# LED_Driver_-_2.net
KiCad netlist of a schematic drawn in Altium Designer
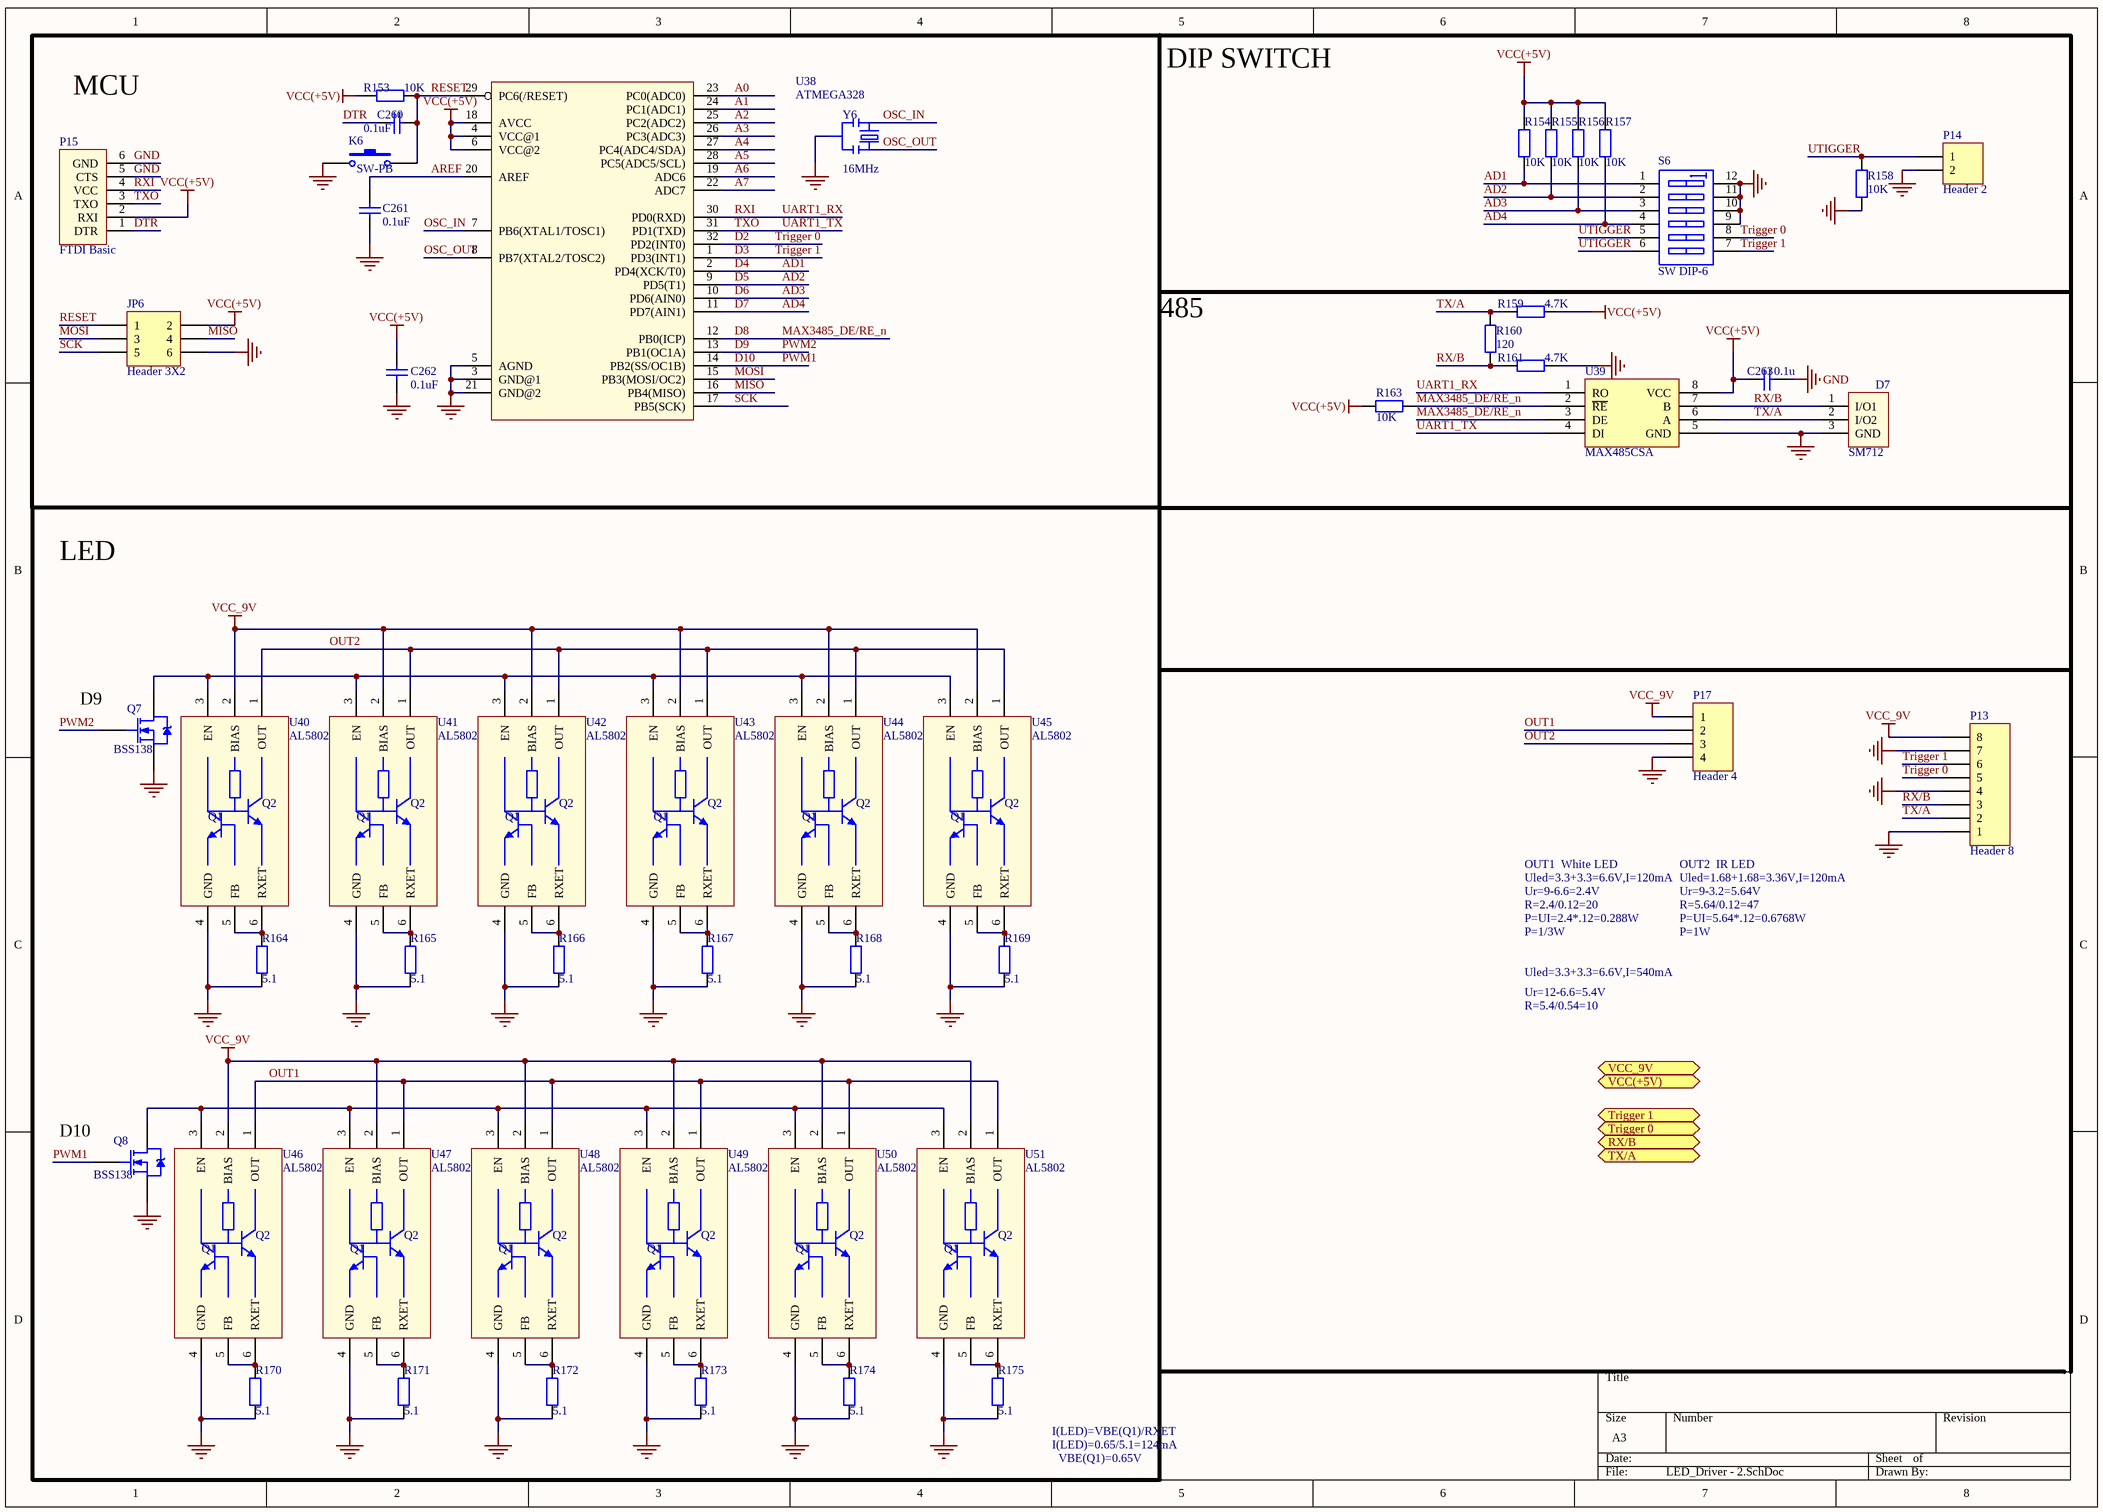
[diagram p0: LED_Driver - 2.SchDoc]

(export (version "E")
  (design (tool "Eeschema 10.0.6"))
  (components
    (comp (ref "C260")
      (value "0.1uF")
      (footprint "C0603")
      (description "Capacitor")
      (fields (field (name "IPARTNUMBER") "C100nF25V10%X7R") (field (name "VOLTAGE") "25V"))
      (libsource (lib "Schlib1") (part "CAP SMT C100nF25V10%X7R"))
    )
    (comp (ref "C261")
      (value "0.1uF")
      (footprint "C0603")
      (description "Capacitor")
      (fields (field (name "IPARTNUMBER") "C100nF25V10%X7R") (field (name "VOLTAGE") "25V"))
      (libsource (lib "Schlib1") (part "CAP SMT C100nF25V10%X7R"))
    )
    (comp (ref "C262")
      (value "0.1uF")
      (footprint "C0603")
      (description "Capacitor")
      (fields (field (name "IPARTNUMBER") "C100nF25V10%X7R") (field (name "VOLTAGE") "25V"))
      (libsource (lib "Schlib1") (part "CAP SMT C100nF25V10%X7R"))
    )
    (comp (ref "C263")
      (value "0.1u")
      (footprint "C0603")
      (description "Capacitor")
      (fields (field (name "PUBLISHER") "Altium Limited"))
      (libsource (lib "Miscellaneous Devices") (part "Cap"))
    )
    (comp (ref "D7")
      (value "SM712")
      (footprint "SOT23-3")
      (libsource (lib "STM32F4_CAM V2.0") (part "SM712"))
    )
    (comp (ref "JP6")
      (value "Header 3X2")
      (footprint "MHDR1X6")
      (description "Header, 3-Pin, Dual row")
      (fields (field (name "PUBLISHER") "Altium Limited"))
      (libsource (lib "Miscellaneous Connectors") (part "Header 3X2"))
    )
    (comp (ref "K6")
      (value "SW-PB")
      (footprint "157SW")
      (description "Switch")
      (fields (field (name "PUBLISHER") "Altium Limited"))
      (libsource (lib "Miscellaneous Devices") (part "SW-PB"))
    )
    (comp (ref "P13")
      (value "Header 8")
      (footprint "SH_1.25MM*8")
      (description "Header, 8-Pin")
      (fields (field (name "PUBLISHER") "Altium Limited"))
      (libsource (lib "Miscellaneous Connectors") (part "Header 8"))
    )
    (comp (ref "P14")
      (value "Header 2")
      (footprint "HDR1X2")
      (description "Header, 2-Pin")
      (fields (field (name "PUBLISHER") "Altium Limited"))
      (libsource (lib "Miscellaneous Connectors") (part "Header 2"))
    )
    (comp (ref "P15")
      (value "FTDI Basic")
      (footprint "MHDR1X6")
      (libsource (lib "PCB_Project1") (part "ARDUINO_SERIAL_PROGRAMPTH"))
    )
    (comp (ref "P17")
      (value "Header 4")
      (footprint "SMT_1.25MM*4")
      (description "Header, 4-Pin")
      (fields (field (name "PUBLISHER") "Altium Limited"))
      (libsource (lib "Miscellaneous Connectors") (part "Header 4"))
    )
    (comp (ref "Q7")
      (value "BSS138")
      (footprint "SOT-23 (Standard)")
      (fields
        (field (name "MANUFACTURER") "Fairchild Semiconductor")
        (field (name "MANUFACTURER PART NUMBER") "BSS123")
      )
      (libsource (lib "Miscellaneous_Devices") (part "NMOS"))
    )
    (comp (ref "Q8")
      (value "BSS138")
      (footprint "SOT-23 (Standard)")
      (fields
        (field (name "MANUFACTURER") "Fairchild Semiconductor")
        (field (name "MANUFACTURER PART NUMBER") "BSS123")
      )
      (libsource (lib "Miscellaneous_Devices") (part "NMOS"))
    )
    (comp (ref "R153")
      (value "10K")
      (footprint "R0603")
      (description "Resistor")
      (libsource (lib "") (part "Res2_2"))
    )
    (comp (ref "R154")
      (value "10K")
      (footprint "R0603")
      (description "Resistor")
      (libsource (lib "") (part "Res2_1"))
    )
    (comp (ref "R155")
      (value "10K")
      (footprint "R0603")
      (description "Resistor")
      (libsource (lib "") (part "Res2_1"))
    )
    (comp (ref "R156")
      (value "10K")
      (footprint "R0603")
      (description "Resistor")
      (libsource (lib "") (part "Res2_1"))
    )
    (comp (ref "R157")
      (value "10K")
      (footprint "R0603")
      (description "Resistor")
      (libsource (lib "") (part "Res2_1"))
    )
    (comp (ref "R158")
      (value "10K")
      (footprint "R0603")
      (description "Resistor")
      (fields (field (name "PUBLISHER") "Altium Limited"))
      (libsource (lib "Miscellaneous Devices") (part "Res2"))
    )
    (comp (ref "R159")
      (value "4.7K")
      (footprint "R0603")
      (description "Resistor")
      (libsource (lib "DM642") (part "Res2"))
    )
    (comp (ref "R160")
      (value "120")
      (footprint "R0603")
      (description "Resistor")
      (libsource (lib "") (part "Res2_1"))
    )
    (comp (ref "R161")
      (value "4.7K")
      (footprint "R0603")
      (description "Resistor")
      (libsource (lib "DM642") (part "Res2"))
    )
    (comp (ref "R163")
      (value "10K")
      (footprint "R0603")
      (description "Resistor")
      (libsource (lib "DM642") (part "Res2"))
    )
    (comp (ref "R164")
      (value "5.1")
      (footprint "R0603")
      (description "Resistor")
      (libsource (lib "") (part "Res2_1"))
    )
    (comp (ref "R165")
      (value "5.1")
      (footprint "R0603")
      (description "Resistor")
      (libsource (lib "") (part "Res2_1"))
    )
    (comp (ref "R166")
      (value "5.1")
      (footprint "R0603")
      (description "Resistor")
      (libsource (lib "") (part "Res2_1"))
    )
    (comp (ref "R167")
      (value "5.1")
      (footprint "R0603")
      (description "Resistor")
      (libsource (lib "") (part "Res2_1"))
    )
    (comp (ref "R168")
      (value "5.1")
      (footprint "R0603")
      (description "Resistor")
      (libsource (lib "") (part "Res2_1"))
    )
    (comp (ref "R169")
      (value "5.1")
      (footprint "R0603")
      (description "Resistor")
      (libsource (lib "") (part "Res2_1"))
    )
    (comp (ref "R170")
      (value "5.1")
      (footprint "R0603")
      (description "Resistor")
      (libsource (lib "") (part "Res2_1"))
    )
    (comp (ref "R171")
      (value "5.1")
      (footprint "R0603")
      (description "Resistor")
      (libsource (lib "") (part "Res2_1"))
    )
    (comp (ref "R172")
      (value "5.1")
      (footprint "R0603")
      (description "Resistor")
      (libsource (lib "") (part "Res2_1"))
    )
    (comp (ref "R173")
      (value "5.1")
      (footprint "R0603")
      (description "Resistor")
      (libsource (lib "") (part "Res2_1"))
    )
    (comp (ref "R174")
      (value "5.1")
      (footprint "R0603")
      (description "Resistor")
      (libsource (lib "") (part "Res2_1"))
    )
    (comp (ref "R175")
      (value "5.1")
      (footprint "R0603")
      (description "Resistor")
      (libsource (lib "") (part "Res2_1"))
    )
    (comp (ref "S6")
      (value "SW DIP-6")
      (footprint "DIP_SW_6WAY_SMD")
      (description "DIP Switch, 6 Position, SPST")
      (fields (field (name "PUBLISHER") "Altium Limited"))
      (libsource (lib "Miscellaneous Devices") (part "SW DIP-6"))
    )
    (comp (ref "U38")
      (value "ATMEGA328")
      (footprint "TQFP32-08")
      (libsource (lib "PCB_Project1") (part "ATMEGA168"))
    )
    (comp (ref "U39")
      (value "MAX485CSA")
      (footprint "SOIC-8")
      (libsource (lib "STM32F4_CAM V1.2") (part "MAX3485CSA"))
    )
    (comp (ref "U40") (value "AL5802") (footprint "SOT26") (libsource (lib "LED") (part "AL5802")))
    (comp (ref "U41") (value "AL5802") (footprint "SOT26") (libsource (lib "LED") (part "AL5802")))
    (comp (ref "U42") (value "AL5802") (footprint "SOT26") (libsource (lib "LED") (part "AL5802")))
    (comp (ref "U43") (value "AL5802") (footprint "SOT26") (libsource (lib "LED") (part "AL5802")))
    (comp (ref "U44") (value "AL5802") (footprint "SOT26") (libsource (lib "LED") (part "AL5802")))
    (comp (ref "U45") (value "AL5802") (footprint "SOT26") (libsource (lib "LED") (part "AL5802")))
    (comp (ref "U46") (value "AL5802") (footprint "SOT26") (libsource (lib "LED") (part "AL5802")))
    (comp (ref "U47") (value "AL5802") (footprint "SOT26") (libsource (lib "LED") (part "AL5802")))
    (comp (ref "U48") (value "AL5802") (footprint "SOT26") (libsource (lib "LED") (part "AL5802")))
    (comp (ref "U49") (value "AL5802") (footprint "SOT26") (libsource (lib "LED") (part "AL5802")))
    (comp (ref "U50") (value "AL5802") (footprint "SOT26") (libsource (lib "LED") (part "AL5802")))
    (comp (ref "U51") (value "AL5802") (footprint "SOT26") (libsource (lib "LED") (part "AL5802")))
    (comp (ref "Y6")
      (value "16MHz")
      (footprint "RESONATOR-SMD")
      (libsource (lib "SparkFun") (part "RESONATORSMD"))
    )
  )
  (nets
    (net (code "1") (name "/A0") (class "Default")
      (node (ref "U38") (pin "23") (pinfunction "PC0(ADC0)_23") (pintype "passive"))
    )
    (net (code "2") (name "/A1") (class "Default")
      (node (ref "U38") (pin "24") (pinfunction "PC1(ADC1)_24") (pintype "passive"))
    )
    (net (code "3") (name "/A2") (class "Default")
      (node (ref "U38") (pin "25") (pinfunction "PC2(ADC2)_25") (pintype "passive"))
    )
    (net (code "4") (name "/A3") (class "Default")
      (node (ref "U38") (pin "26") (pinfunction "PC3(ADC3)_26") (pintype "passive"))
    )
    (net (code "5") (name "/A4") (class "Default")
      (node (ref "U38") (pin "27") (pinfunction "PC4(ADC4/SDA)_27") (pintype "passive"))
    )
    (net (code "6") (name "/A5") (class "Default")
      (node (ref "U38") (pin "28") (pinfunction "PC5(ADC5/SCL)_28") (pintype "passive"))
    )
    (net (code "7") (name "/A6") (class "Default")
      (node (ref "U38") (pin "19") (pinfunction "ADC6_19") (pintype "passive"))
    )
    (net (code "8") (name "/A7") (class "Default")
      (node (ref "U38") (pin "22") (pinfunction "ADC7_22") (pintype "passive"))
    )
    (net (code "9") (name "/AD1") (class "Default")
      (node (ref "R154") (pin "2") (pinfunction "2_2") (pintype "passive"))
      (node (ref "S6") (pin "1") (pinfunction "A1_1") (pintype "passive"))
      (node (ref "U38") (pin "2") (pinfunction "PD4(XCK/T0)_2") (pintype "passive"))
    )
    (net (code "10") (name "/AD2") (class "Default")
      (node (ref "R155") (pin "2") (pinfunction "2_2") (pintype "passive"))
      (node (ref "S6") (pin "2") (pinfunction "A2_2") (pintype "passive"))
      (node (ref "U38") (pin "9") (pinfunction "PD5(T1)_9") (pintype "passive"))
    )
    (net (code "11") (name "/AD3") (class "Default")
      (node (ref "R156") (pin "2") (pinfunction "2_2") (pintype "passive"))
      (node (ref "S6") (pin "3") (pinfunction "A3_3") (pintype "passive"))
      (node (ref "U38") (pin "10") (pinfunction "PD6(AIN0)_10") (pintype "passive"))
    )
    (net (code "12") (name "/AD4") (class "Default")
      (node (ref "R157") (pin "2") (pinfunction "2_2") (pintype "passive"))
      (node (ref "S6") (pin "4") (pinfunction "A4_4") (pintype "passive"))
      (node (ref "U38") (pin "11") (pinfunction "PD7(AIN1)_11") (pintype "passive"))
    )
    (net (code "13") (name "/AREF") (class "Default")
      (node (ref "C261") (pin "2") (pinfunction "2_2") (pintype "passive"))
      (node (ref "U38") (pin "20") (pinfunction "AREF_20") (pintype "passive"))
    )
    (net (code "14") (name "/D2") (class "Default")
      (node (ref "P13") (pin "5") (pinfunction "5_5") (pintype "passive"))
      (node (ref "S6") (pin "8") (pinfunction "B5_8") (pintype "passive"))
      (node (ref "U38") (pin "32") (pinfunction "PD2(INT0)_32") (pintype "passive"))
    )
    (net (code "15") (name "/D3") (class "Default")
      (node (ref "P13") (pin "6") (pinfunction "6_6") (pintype "passive"))
      (node (ref "S6") (pin "7") (pinfunction "B6_7") (pintype "passive"))
      (node (ref "U38") (pin "1") (pinfunction "PD3(INT1)_1") (pintype "passive"))
    )
    (net (code "16") (name "/D8") (class "Default")
      (node (ref "R163") (pin "1") (pinfunction "1_1") (pintype "passive"))
      (node (ref "U38") (pin "12") (pinfunction "PB0(ICP)_12") (pintype "passive"))
      (node (ref "U39") (pin "2") (pinfunction "~{RE}_2") (pintype "passive"))
      (node (ref "U39") (pin "3") (pinfunction "DE_3") (pintype "passive"))
    )
    (net (code "17") (name "/D9") (class "Default")
      (node (ref "Q7") (pin "G") (pinfunction "G_G") (pintype "passive"))
      (node (ref "U38") (pin "13") (pinfunction "PB1(OC1A)_13") (pintype "passive"))
    )
    (net (code "18") (name "/D10") (class "Default")
      (node (ref "Q8") (pin "G") (pinfunction "G_G") (pintype "passive"))
      (node (ref "U38") (pin "14") (pinfunction "PB2(SS/OC1B)_14") (pintype "passive"))
    )
    (net (code "19") (name "/DTR") (class "Default")
      (node (ref "C260") (pin "1") (pinfunction "1_1") (pintype "passive"))
      (node (ref "P15") (pin "1") (pinfunction "DTR_1") (pintype "passive"))
    )
    (net (code "20") (name "/MISO") (class "Default")
      (node (ref "JP6") (pin "4") (pinfunction "4_4") (pintype "passive"))
      (node (ref "U38") (pin "16") (pinfunction "PB4(MISO)_16") (pintype "passive"))
    )
    (net (code "21") (name "/MOSI") (class "Default")
      (node (ref "JP6") (pin "3") (pinfunction "3_3") (pintype "passive"))
      (node (ref "U38") (pin "15") (pinfunction "PB3(MOSI/OC2)_15") (pintype "passive"))
    )
    (net (code "22") (name "/OSC_IN") (class "Default")
      (node (ref "U38") (pin "7") (pinfunction "PB6(XTAL1/TOSC1)_7") (pintype "passive"))
      (node (ref "Y6") (pin "3") (pinfunction "3_3") (pintype "passive"))
    )
    (net (code "23") (name "/OSC_OUT") (class "Default")
      (node (ref "U38") (pin "8") (pinfunction "PB7(XTAL2/TOSC2)_8") (pintype "passive"))
      (node (ref "Y6") (pin "1") (pinfunction "1_1") (pintype "passive"))
    )
    (net (code "24") (name "/OUT1") (class "Default")
      (node (ref "P17") (pin "2") (pinfunction "2_2") (pintype "passive"))
      (node (ref "U46") (pin "1") (pinfunction "OUT_1") (pintype "passive"))
      (node (ref "U47") (pin "1") (pinfunction "OUT_1") (pintype "passive"))
      (node (ref "U48") (pin "1") (pinfunction "OUT_1") (pintype "passive"))
      (node (ref "U49") (pin "1") (pinfunction "OUT_1") (pintype "passive"))
      (node (ref "U50") (pin "1") (pinfunction "OUT_1") (pintype "passive"))
      (node (ref "U51") (pin "1") (pinfunction "OUT_1") (pintype "passive"))
    )
    (net (code "25") (name "/OUT2") (class "Default")
      (node (ref "P17") (pin "3") (pinfunction "3_3") (pintype "passive"))
      (node (ref "U40") (pin "1") (pinfunction "OUT_1") (pintype "passive"))
      (node (ref "U41") (pin "1") (pinfunction "OUT_1") (pintype "passive"))
      (node (ref "U42") (pin "1") (pinfunction "OUT_1") (pintype "passive"))
      (node (ref "U43") (pin "1") (pinfunction "OUT_1") (pintype "passive"))
      (node (ref "U44") (pin "1") (pinfunction "OUT_1") (pintype "passive"))
      (node (ref "U45") (pin "1") (pinfunction "OUT_1") (pintype "passive"))
    )
    (net (code "26") (name "/RESET") (class "Default")
      (node (ref "C260") (pin "2") (pinfunction "2_2") (pintype "passive"))
      (node (ref "JP6") (pin "1") (pinfunction "1_1") (pintype "passive"))
      (node (ref "K6") (pin "2") (pinfunction "2_2") (pintype "passive"))
      (node (ref "R153") (pin "2") (pinfunction "2_2") (pintype "passive"))
      (node (ref "U38") (pin "29") (pinfunction "PC6(/RESET)_29") (pintype "passive"))
    )
    (net (code "27") (name "/RXI") (class "Default")
      (node (ref "P15") (pin "4") (pinfunction "VCC_4") (pintype "passive"))
      (node (ref "U38") (pin "30") (pinfunction "PD0(RXD)_30") (pintype "passive"))
      (node (ref "U39") (pin "1") (pinfunction "RO_1") (pintype "passive"))
    )
    (net (code "28") (name "/RX{slash}B") (class "Default")
      (node (ref "D7") (pin "1") (pinfunction "I/O1_1") (pintype "passive"))
      (node (ref "P13") (pin "3") (pinfunction "3_3") (pintype "passive"))
      (node (ref "R160") (pin "2") (pinfunction "2_2") (pintype "passive"))
      (node (ref "R161") (pin "2") (pinfunction "2_2") (pintype "passive"))
      (node (ref "U39") (pin "7") (pinfunction "B_7") (pintype "passive"))
    )
    (net (code "29") (name "/SCK") (class "Default")
      (node (ref "JP6") (pin "5") (pinfunction "5_5") (pintype "passive"))
      (node (ref "U38") (pin "17") (pinfunction "PB5(SCK)_17") (pintype "passive"))
    )
    (net (code "30") (name "/TXO") (class "Default")
      (node (ref "P15") (pin "3") (pinfunction "TXO_3") (pintype "passive"))
      (node (ref "U38") (pin "31") (pinfunction "PD1(TXD)_31") (pintype "passive"))
      (node (ref "U39") (pin "4") (pinfunction "DI_4") (pintype "passive"))
    )
    (net (code "31") (name "/TX{slash}A") (class "Default")
      (node (ref "D7") (pin "2") (pinfunction "I/O2_2") (pintype "passive"))
      (node (ref "P13") (pin "2") (pinfunction "2_2") (pintype "passive"))
      (node (ref "R159") (pin "2") (pinfunction "2_2") (pintype "passive"))
      (node (ref "R160") (pin "1") (pinfunction "1_1") (pintype "passive"))
      (node (ref "U39") (pin "6") (pinfunction "A_6") (pintype "passive"))
    )
    (net (code "32") (name "/UTIGGER") (class "Default")
      (node (ref "P14") (pin "1") (pinfunction "1_1") (pintype "passive"))
      (node (ref "R158") (pin "2") (pinfunction "2_2") (pintype "passive"))
      (node (ref "S6") (pin "5") (pinfunction "A5_5") (pintype "passive"))
      (node (ref "S6") (pin "6") (pinfunction "A6_6") (pintype "passive"))
    )
    (net (code "33") (name "GND") (class "Default")
      (node (ref "C261") (pin "1") (pinfunction "1_1") (pintype "passive"))
      (node (ref "C262") (pin "2") (pinfunction "2_2") (pintype "passive"))
      (node (ref "C263") (pin "1") (pinfunction "1_1") (pintype "passive"))
      (node (ref "D7") (pin "3") (pinfunction "GND_3") (pintype "passive"))
      (node (ref "JP6") (pin "6") (pinfunction "6_6") (pintype "passive"))
      (node (ref "K6") (pin "1") (pinfunction "1_1") (pintype "passive"))
      (node (ref "P13") (pin "1") (pinfunction "1_1") (pintype "passive"))
      (node (ref "P13") (pin "4") (pinfunction "4_4") (pintype "passive"))
      (node (ref "P13") (pin "7") (pinfunction "7_7") (pintype "passive"))
      (node (ref "P14") (pin "2") (pinfunction "2_2") (pintype "passive"))
      (node (ref "P15") (pin "5") (pinfunction "CTS_5") (pintype "passive"))
      (node (ref "P15") (pin "6") (pinfunction "GND_6") (pintype "passive"))
      (node (ref "P17") (pin "4") (pinfunction "4_4") (pintype "passive"))
      (node (ref "Q7") (pin "S") (pinfunction "S_S") (pintype "passive"))
      (node (ref "Q8") (pin "S") (pinfunction "S_S") (pintype "passive"))
      (node (ref "R158") (pin "1") (pinfunction "1_1") (pintype "passive"))
      (node (ref "R161") (pin "1") (pinfunction "1_1") (pintype "passive"))
      (node (ref "R164") (pin "2") (pinfunction "2_2") (pintype "passive"))
      (node (ref "R165") (pin "2") (pinfunction "2_2") (pintype "passive"))
      (node (ref "R166") (pin "2") (pinfunction "2_2") (pintype "passive"))
      (node (ref "R167") (pin "2") (pinfunction "2_2") (pintype "passive"))
      (node (ref "R168") (pin "2") (pinfunction "2_2") (pintype "passive"))
      (node (ref "R169") (pin "2") (pinfunction "2_2") (pintype "passive"))
      (node (ref "R170") (pin "2") (pinfunction "2_2") (pintype "passive"))
      (node (ref "R171") (pin "2") (pinfunction "2_2") (pintype "passive"))
      (node (ref "R172") (pin "2") (pinfunction "2_2") (pintype "passive"))
      (node (ref "R173") (pin "2") (pinfunction "2_2") (pintype "passive"))
      (node (ref "R174") (pin "2") (pinfunction "2_2") (pintype "passive"))
      (node (ref "R175") (pin "2") (pinfunction "2_2") (pintype "passive"))
      (node (ref "S6") (pin "10") (pinfunction "B3_10") (pintype "passive"))
      (node (ref "S6") (pin "11") (pinfunction "B2_11") (pintype "passive"))
      (node (ref "S6") (pin "12") (pinfunction "B1_12") (pintype "passive"))
      (node (ref "S6") (pin "9") (pinfunction "B4_9") (pintype "passive"))
      (node (ref "U38") (pin "21") (pinfunction "GND@2_21") (pintype "passive"))
      (node (ref "U38") (pin "3") (pinfunction "GND@1_3") (pintype "passive"))
      (node (ref "U38") (pin "5") (pinfunction "AGND_5") (pintype "passive"))
      (node (ref "U39") (pin "5") (pinfunction "GND_5") (pintype "passive"))
      (node (ref "U40") (pin "4") (pinfunction "GND_4") (pintype "passive"))
      (node (ref "U41") (pin "4") (pinfunction "GND_4") (pintype "passive"))
      (node (ref "U42") (pin "4") (pinfunction "GND_4") (pintype "passive"))
      (node (ref "U43") (pin "4") (pinfunction "GND_4") (pintype "passive"))
      (node (ref "U44") (pin "4") (pinfunction "GND_4") (pintype "passive"))
      (node (ref "U45") (pin "4") (pinfunction "GND_4") (pintype "passive"))
      (node (ref "U46") (pin "4") (pinfunction "GND_4") (pintype "passive"))
      (node (ref "U47") (pin "4") (pinfunction "GND_4") (pintype "passive"))
      (node (ref "U48") (pin "4") (pinfunction "GND_4") (pintype "passive"))
      (node (ref "U49") (pin "4") (pinfunction "GND_4") (pintype "passive"))
      (node (ref "U50") (pin "4") (pinfunction "GND_4") (pintype "passive"))
      (node (ref "U51") (pin "4") (pinfunction "GND_4") (pintype "passive"))
      (node (ref "Y6") (pin "2") (pinfunction "2_2") (pintype "passive"))
    )
    (net (code "34") (name "Net-(U40-EN)") (class "Default")
      (node (ref "Q7") (pin "D") (pinfunction "D_D") (pintype "passive"))
      (node (ref "U40") (pin "3") (pinfunction "EN_3") (pintype "passive"))
      (node (ref "U41") (pin "3") (pinfunction "EN_3") (pintype "passive"))
      (node (ref "U42") (pin "3") (pinfunction "EN_3") (pintype "passive"))
      (node (ref "U43") (pin "3") (pinfunction "EN_3") (pintype "passive"))
      (node (ref "U44") (pin "3") (pinfunction "EN_3") (pintype "passive"))
      (node (ref "U45") (pin "3") (pinfunction "EN_3") (pintype "passive"))
    )
    (net (code "35") (name "Net-(U40-FB)") (class "Default")
      (node (ref "R164") (pin "1") (pinfunction "1_1") (pintype "passive"))
      (node (ref "U40") (pin "5") (pinfunction "FB_5") (pintype "passive"))
      (node (ref "U40") (pin "6") (pinfunction "RXET_6") (pintype "passive"))
    )
    (net (code "36") (name "Net-(U41-FB)") (class "Default")
      (node (ref "R165") (pin "1") (pinfunction "1_1") (pintype "passive"))
      (node (ref "U41") (pin "5") (pinfunction "FB_5") (pintype "passive"))
      (node (ref "U41") (pin "6") (pinfunction "RXET_6") (pintype "passive"))
    )
    (net (code "37") (name "Net-(U42-FB)") (class "Default")
      (node (ref "R166") (pin "1") (pinfunction "1_1") (pintype "passive"))
      (node (ref "U42") (pin "5") (pinfunction "FB_5") (pintype "passive"))
      (node (ref "U42") (pin "6") (pinfunction "RXET_6") (pintype "passive"))
    )
    (net (code "38") (name "Net-(U43-FB)") (class "Default")
      (node (ref "R167") (pin "1") (pinfunction "1_1") (pintype "passive"))
      (node (ref "U43") (pin "5") (pinfunction "FB_5") (pintype "passive"))
      (node (ref "U43") (pin "6") (pinfunction "RXET_6") (pintype "passive"))
    )
    (net (code "39") (name "Net-(U44-FB)") (class "Default")
      (node (ref "R168") (pin "1") (pinfunction "1_1") (pintype "passive"))
      (node (ref "U44") (pin "5") (pinfunction "FB_5") (pintype "passive"))
      (node (ref "U44") (pin "6") (pinfunction "RXET_6") (pintype "passive"))
    )
    (net (code "40") (name "Net-(U45-FB)") (class "Default")
      (node (ref "R169") (pin "1") (pinfunction "1_1") (pintype "passive"))
      (node (ref "U45") (pin "5") (pinfunction "FB_5") (pintype "passive"))
      (node (ref "U45") (pin "6") (pinfunction "RXET_6") (pintype "passive"))
    )
    (net (code "41") (name "Net-(U46-EN)") (class "Default")
      (node (ref "Q8") (pin "D") (pinfunction "D_D") (pintype "passive"))
      (node (ref "U46") (pin "3") (pinfunction "EN_3") (pintype "passive"))
      (node (ref "U47") (pin "3") (pinfunction "EN_3") (pintype "passive"))
      (node (ref "U48") (pin "3") (pinfunction "EN_3") (pintype "passive"))
      (node (ref "U49") (pin "3") (pinfunction "EN_3") (pintype "passive"))
      (node (ref "U50") (pin "3") (pinfunction "EN_3") (pintype "passive"))
      (node (ref "U51") (pin "3") (pinfunction "EN_3") (pintype "passive"))
    )
    (net (code "42") (name "Net-(U46-FB)") (class "Default")
      (node (ref "R170") (pin "1") (pinfunction "1_1") (pintype "passive"))
      (node (ref "U46") (pin "5") (pinfunction "FB_5") (pintype "passive"))
      (node (ref "U46") (pin "6") (pinfunction "RXET_6") (pintype "passive"))
    )
    (net (code "43") (name "Net-(U47-FB)") (class "Default")
      (node (ref "R171") (pin "1") (pinfunction "1_1") (pintype "passive"))
      (node (ref "U47") (pin "5") (pinfunction "FB_5") (pintype "passive"))
      (node (ref "U47") (pin "6") (pinfunction "RXET_6") (pintype "passive"))
    )
    (net (code "44") (name "Net-(U48-FB)") (class "Default")
      (node (ref "R172") (pin "1") (pinfunction "1_1") (pintype "passive"))
      (node (ref "U48") (pin "5") (pinfunction "FB_5") (pintype "passive"))
      (node (ref "U48") (pin "6") (pinfunction "RXET_6") (pintype "passive"))
    )
    (net (code "45") (name "Net-(U49-FB)") (class "Default")
      (node (ref "R173") (pin "1") (pinfunction "1_1") (pintype "passive"))
      (node (ref "U49") (pin "5") (pinfunction "FB_5") (pintype "passive"))
      (node (ref "U49") (pin "6") (pinfunction "RXET_6") (pintype "passive"))
    )
    (net (code "46") (name "Net-(U50-FB)") (class "Default")
      (node (ref "R174") (pin "1") (pinfunction "1_1") (pintype "passive"))
      (node (ref "U50") (pin "5") (pinfunction "FB_5") (pintype "passive"))
      (node (ref "U50") (pin "6") (pinfunction "RXET_6") (pintype "passive"))
    )
    (net (code "47") (name "Net-(U51-FB)") (class "Default")
      (node (ref "R175") (pin "1") (pinfunction "1_1") (pintype "passive"))
      (node (ref "U51") (pin "5") (pinfunction "FB_5") (pintype "passive"))
      (node (ref "U51") (pin "6") (pinfunction "RXET_6") (pintype "passive"))
    )
    (net (code "48") (name "VCC(+5V)") (class "Default")
      (node (ref "C262") (pin "1") (pinfunction "1_1") (pintype "passive"))
      (node (ref "C263") (pin "2") (pinfunction "2_2") (pintype "passive"))
      (node (ref "JP6") (pin "2") (pinfunction "2_2") (pintype "passive"))
      (node (ref "P15") (pin "2") (pinfunction "RXI_2") (pintype "passive"))
      (node (ref "R153") (pin "1") (pinfunction "1_1") (pintype "passive"))
      (node (ref "R154") (pin "1") (pinfunction "1_1") (pintype "passive"))
      (node (ref "R155") (pin "1") (pinfunction "1_1") (pintype "passive"))
      (node (ref "R156") (pin "1") (pinfunction "1_1") (pintype "passive"))
      (node (ref "R157") (pin "1") (pinfunction "1_1") (pintype "passive"))
      (node (ref "R159") (pin "1") (pinfunction "1_1") (pintype "passive"))
      (node (ref "R163") (pin "2") (pinfunction "2_2") (pintype "passive"))
      (node (ref "U38") (pin "18") (pinfunction "AVCC_18") (pintype "passive"))
      (node (ref "U38") (pin "4") (pinfunction "VCC@1_4") (pintype "passive"))
      (node (ref "U38") (pin "6") (pinfunction "VCC@2_6") (pintype "passive"))
      (node (ref "U39") (pin "8") (pinfunction "VCC_8") (pintype "passive"))
    )
    (net (code "49") (name "VCC_9V") (class "Default")
      (node (ref "P13") (pin "8") (pinfunction "8_8") (pintype "passive"))
      (node (ref "P17") (pin "1") (pinfunction "1_1") (pintype "passive"))
      (node (ref "U40") (pin "2") (pinfunction "BIAS_2") (pintype "passive"))
      (node (ref "U41") (pin "2") (pinfunction "BIAS_2") (pintype "passive"))
      (node (ref "U42") (pin "2") (pinfunction "BIAS_2") (pintype "passive"))
      (node (ref "U43") (pin "2") (pinfunction "BIAS_2") (pintype "passive"))
      (node (ref "U44") (pin "2") (pinfunction "BIAS_2") (pintype "passive"))
      (node (ref "U45") (pin "2") (pinfunction "BIAS_2") (pintype "passive"))
      (node (ref "U46") (pin "2") (pinfunction "BIAS_2") (pintype "passive"))
      (node (ref "U47") (pin "2") (pinfunction "BIAS_2") (pintype "passive"))
      (node (ref "U48") (pin "2") (pinfunction "BIAS_2") (pintype "passive"))
      (node (ref "U49") (pin "2") (pinfunction "BIAS_2") (pintype "passive"))
      (node (ref "U50") (pin "2") (pinfunction "BIAS_2") (pintype "passive"))
      (node (ref "U51") (pin "2") (pinfunction "BIAS_2") (pintype "passive"))
    )
  )
)
